# Adafruit_MAX98306.net
KiCad netlist of a schematic drawn in EAGLE
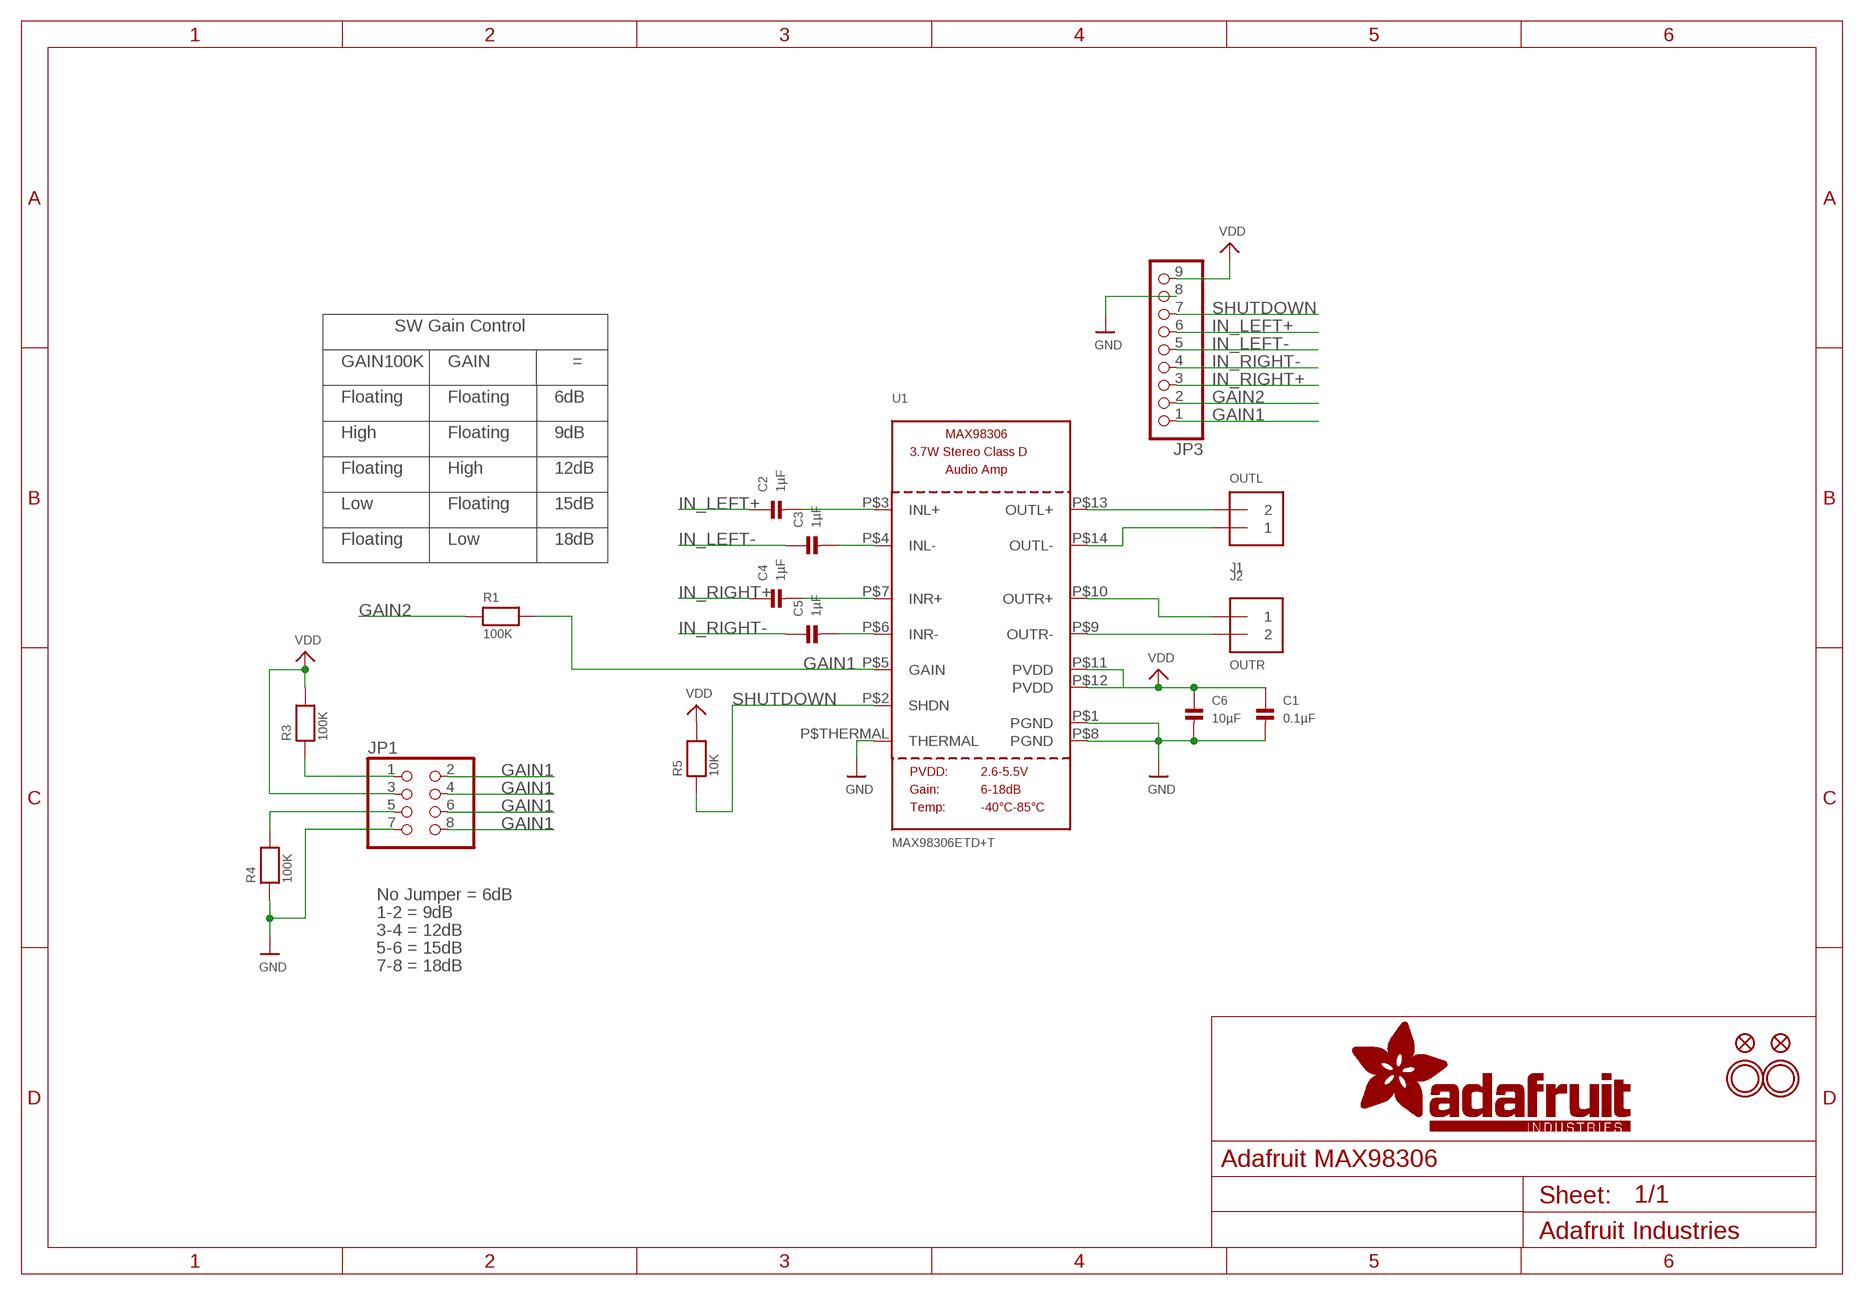
[diagram p0: schematic, sheet 1]

(export (version "E")
  (design (tool "Eeschema 10.0.6"))
  (components
    (comp (ref "C1")
      (value "0.1µF")
      (footprint "eagle-import:0805")
      (libsource (lib "eagle-import") (part "CAP_CERAMIC0805"))
    )
    (comp (ref "C2")
      (value "1µF")
      (footprint "eagle-import:0805")
      (libsource (lib "eagle-import") (part "CAP_CERAMIC0805"))
    )
    (comp (ref "C3")
      (value "1µF")
      (footprint "eagle-import:0805")
      (libsource (lib "eagle-import") (part "CAP_CERAMIC0805"))
    )
    (comp (ref "C4")
      (value "1µF")
      (footprint "eagle-import:0805")
      (libsource (lib "eagle-import") (part "CAP_CERAMIC0805"))
    )
    (comp (ref "C5")
      (value "1µF")
      (footprint "eagle-import:0805")
      (libsource (lib "eagle-import") (part "CAP_CERAMIC0805"))
    )
    (comp (ref "C6")
      (value "10µF")
      (footprint "eagle-import:0805")
      (libsource (lib "eagle-import") (part "CAP_CERAMIC0805"))
    )
    (comp (ref "FID1")
      (value "FIDUCIAL\"\"")
      (footprint "eagle-import:FIDUCIAL_1MM")
      (libsource (lib "eagle-import") (part "FIDUCIAL{dblquote}{dblquote}"))
    )
    (comp (ref "FID2")
      (value "FIDUCIAL\"\"")
      (footprint "eagle-import:FIDUCIAL_1MM")
      (libsource (lib "eagle-import") (part "FIDUCIAL{dblquote}{dblquote}"))
    )
    (comp (ref "J1")
      (value "OUTL")
      (footprint "eagle-import:TERMBLOCK_1X2-3.5MM")
      (libsource (lib "eagle-import") (part "TERMBLOCK_1X2"))
    )
    (comp (ref "J2")
      (value "OUTR")
      (footprint "eagle-import:TERMBLOCK_1X2-3.5MM")
      (libsource (lib "eagle-import") (part "TERMBLOCK_1X2"))
    )
    (comp (ref "JP1")
      (value "PINHD-2X4")
      (footprint "eagle-import:2X04")
      (libsource (lib "eagle-import") (part "PINHD-2X4"))
    )
    (comp (ref "JP3")
      (value "HEADER-1X970MIL")
      (footprint "eagle-import:1X09_ROUND_70")
      (libsource (lib "eagle-import") (part "HEADER-1X970MIL"))
    )
    (comp (ref "R1")
      (value "100K")
      (footprint "eagle-import:0805")
      (libsource (lib "eagle-import") (part "RESISTOR0805"))
    )
    (comp (ref "R3")
      (value "100K")
      (footprint "eagle-import:0805")
      (libsource (lib "eagle-import") (part "RESISTOR0805"))
    )
    (comp (ref "R4")
      (value "100K")
      (footprint "eagle-import:0805")
      (libsource (lib "eagle-import") (part "RESISTOR0805"))
    )
    (comp (ref "R5")
      (value "10K")
      (footprint "eagle-import:0805")
      (libsource (lib "eagle-import") (part "RESISTOR0805"))
    )
    (comp (ref "U$6")
      (value "MOUNTINGHOLE2.5")
      (footprint "eagle-import:MOUNTINGHOLE_2.5_PLATED")
      (libsource (lib "eagle-import") (part "MOUNTINGHOLE2.5"))
    )
    (comp (ref "U$7")
      (value "MOUNTINGHOLE2.5")
      (footprint "eagle-import:MOUNTINGHOLE_2.5_PLATED")
      (libsource (lib "eagle-import") (part "MOUNTINGHOLE2.5"))
    )
    (comp (ref "U1")
      (value "MAX98306ETD+T")
      (footprint "eagle-import:TDFN14_3X3MM")
      (libsource (lib "eagle-import") (part "AUDIOAMP_MAX98306"))
    )
  )
  (nets
    (net (code "1") (name "/GAIN1") (class "Default")
      (node (ref "JP1") (pin "2") (pinfunction "2_2") (pintype "passive"))
      (node (ref "JP1") (pin "4") (pinfunction "4_4") (pintype "passive"))
      (node (ref "JP1") (pin "6") (pinfunction "6_6") (pintype "passive"))
      (node (ref "JP1") (pin "8") (pinfunction "8_8") (pintype "passive"))
      (node (ref "JP3") (pin "1") (pinfunction "1_1") (pintype "passive"))
      (node (ref "R1") (pin "2") (pinfunction "2_2") (pintype "passive"))
      (node (ref "U1") (pin "P$5") (pinfunction "GAIN_P$5") (pintype "input"))
    )
    (net (code "2") (name "/GAIN2") (class "Default")
      (node (ref "JP3") (pin "2") (pinfunction "2_2") (pintype "passive"))
      (node (ref "R1") (pin "1") (pinfunction "1_1") (pintype "passive"))
    )
    (net (code "3") (name "/IN_LEFT+") (class "Default")
      (node (ref "C2") (pin "1") (pinfunction "P$1_1") (pintype "passive"))
      (node (ref "JP3") (pin "6") (pinfunction "6_6") (pintype "passive"))
    )
    (net (code "4") (name "/IN_LEFT-") (class "Default")
      (node (ref "C3") (pin "1") (pinfunction "P$1_1") (pintype "passive"))
      (node (ref "JP3") (pin "5") (pinfunction "5_5") (pintype "passive"))
    )
    (net (code "5") (name "/IN_RIGHT+") (class "Default")
      (node (ref "C4") (pin "1") (pinfunction "P$1_1") (pintype "passive"))
      (node (ref "JP3") (pin "3") (pinfunction "3_3") (pintype "passive"))
    )
    (net (code "6") (name "/IN_RIGHT-") (class "Default")
      (node (ref "C5") (pin "1") (pinfunction "P$1_1") (pintype "passive"))
      (node (ref "JP3") (pin "4") (pinfunction "4_4") (pintype "passive"))
    )
    (net (code "7") (name "/SHUTDOWN") (class "Default")
      (node (ref "JP3") (pin "7") (pinfunction "7_7") (pintype "passive"))
      (node (ref "R5") (pin "1") (pinfunction "1_1") (pintype "passive"))
      (node (ref "U1") (pin "P$2") (pinfunction "SHDN_P$2") (pintype "input"))
    )
    (net (code "8") (name "GND") (class "Default")
      (node (ref "C1") (pin "2") (pinfunction "P$2_2") (pintype "passive"))
      (node (ref "C6") (pin "2") (pinfunction "P$2_2") (pintype "passive"))
      (node (ref "JP1") (pin "7") (pinfunction "7_7") (pintype "passive"))
      (node (ref "JP3") (pin "8") (pinfunction "8_8") (pintype "passive"))
      (node (ref "R4") (pin "1") (pinfunction "1_1") (pintype "passive"))
      (node (ref "U1") (pin "P$1") (pinfunction "PGND_P$1") (pintype "power_in"))
      (node (ref "U1") (pin "P$8") (pinfunction "PGND_P$8") (pintype "power_in"))
      (node (ref "U1") (pin "P$THERMAL") (pinfunction "THERMAL_P$THERMAL") (pintype "power_in"))
    )
    (net (code "9") (name "Net-(C2-P$2)") (class "Default")
      (node (ref "C2") (pin "2") (pinfunction "P$2_2") (pintype "passive"))
      (node (ref "U1") (pin "P$3") (pinfunction "INL+_P$3") (pintype "input"))
    )
    (net (code "10") (name "Net-(C3-P$2)") (class "Default")
      (node (ref "C3") (pin "2") (pinfunction "P$2_2") (pintype "passive"))
      (node (ref "U1") (pin "P$4") (pinfunction "INL-_P$4") (pintype "input"))
    )
    (net (code "11") (name "Net-(C4-P$2)") (class "Default")
      (node (ref "C4") (pin "2") (pinfunction "P$2_2") (pintype "passive"))
      (node (ref "U1") (pin "P$7") (pinfunction "INR+_P$7") (pintype "input"))
    )
    (net (code "12") (name "Net-(C5-P$2)") (class "Default")
      (node (ref "C5") (pin "2") (pinfunction "P$2_2") (pintype "passive"))
      (node (ref "U1") (pin "P$6") (pinfunction "INR-_P$6") (pintype "input"))
    )
    (net (code "13") (name "Net-(JP1-Pad1)") (class "Default")
      (node (ref "JP1") (pin "1") (pinfunction "1_1") (pintype "passive"))
      (node (ref "R3") (pin "1") (pinfunction "1_1") (pintype "passive"))
    )
    (net (code "14") (name "Net-(JP1-Pad5)") (class "Default")
      (node (ref "JP1") (pin "5") (pinfunction "5_5") (pintype "passive"))
      (node (ref "R4") (pin "2") (pinfunction "2_2") (pintype "passive"))
    )
    (net (code "15") (name "Net-(U1-OUTL+)") (class "Default")
      (node (ref "J1") (pin "2") (pinfunction "2_2") (pintype "passive"))
      (node (ref "U1") (pin "P$13") (pinfunction "OUTL+_P$13") (pintype "output"))
    )
    (net (code "16") (name "Net-(U1-OUTL-)") (class "Default")
      (node (ref "J1") (pin "1") (pinfunction "1_1") (pintype "passive"))
      (node (ref "U1") (pin "P$14") (pinfunction "OUTL-_P$14") (pintype "output"))
    )
    (net (code "17") (name "Net-(U1-OUTR+)") (class "Default")
      (node (ref "J2") (pin "1") (pinfunction "1_1") (pintype "passive"))
      (node (ref "U1") (pin "P$10") (pinfunction "OUTR+_P$10") (pintype "output"))
    )
    (net (code "18") (name "Net-(U1-OUTR-)") (class "Default")
      (node (ref "J2") (pin "2") (pinfunction "2_2") (pintype "passive"))
      (node (ref "U1") (pin "P$9") (pinfunction "OUTR-_P$9") (pintype "output"))
    )
    (net (code "19") (name "VDD") (class "Default")
      (node (ref "C1") (pin "1") (pinfunction "P$1_1") (pintype "passive"))
      (node (ref "C6") (pin "1") (pinfunction "P$1_1") (pintype "passive"))
      (node (ref "JP1") (pin "3") (pinfunction "3_3") (pintype "passive"))
      (node (ref "JP3") (pin "9") (pinfunction "9_9") (pintype "passive"))
      (node (ref "R3") (pin "2") (pinfunction "2_2") (pintype "passive"))
      (node (ref "R5") (pin "2") (pinfunction "2_2") (pintype "passive"))
      (node (ref "U1") (pin "P$11") (pinfunction "PVDD_P$11") (pintype "power_in"))
      (node (ref "U1") (pin "P$12") (pinfunction "PVDD_P$12") (pintype "power_in"))
    )
  )
)
